# op-amp.net
KiCad netlist of a schematic drawn in Altium Designer
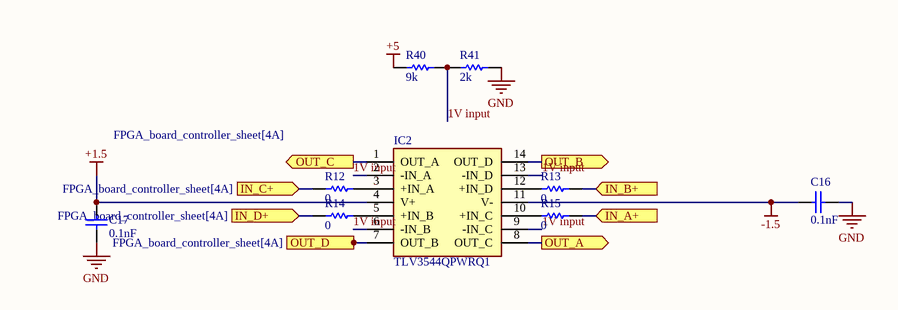
[diagram p0: op-amp.SchDoc]

(export (version "E")
  (design (tool "Eeschema 10.0.6"))
  (components
    (comp (ref "C16")
      (value "0.1nF")
      (footprint "C0603")
      (libsource (lib "Schlib_FPGA_Controller") (part "Cap"))
    )
    (comp (ref "C17")
      (value "0.1nF")
      (footprint "C0603")
      (libsource (lib "Schlib_FPGA_Controller") (part "Cap"))
    )
    (comp (ref "IC2")
      (value "TLV3544QPWRQ1")
      (footprint "SamacSys:SOP65P640X120-14N")
      (description "Integrated Circuit")
      (fields (field (name "MOUSER PART NUMBER") "595-TLV3544QPWRQ1"))
      (libsource (lib "Schlib_FPGA_Controller") (part "TLV3544QPWRQ1"))
    )
    (comp (ref "R12")
      (value "0")
      (footprint "R0603")
      (libsource (lib "Schlib_FPGA_Controller") (part "Resistor"))
    )
    (comp (ref "R13")
      (value "0")
      (footprint "R0603")
      (libsource (lib "Schlib_FPGA_Controller") (part "Resistor"))
    )
    (comp (ref "R14")
      (value "0")
      (footprint "R0603")
      (libsource (lib "Schlib_FPGA_Controller") (part "Resistor"))
    )
    (comp (ref "R15")
      (value "0")
      (footprint "R0603")
      (libsource (lib "Schlib_FPGA_Controller") (part "Resistor"))
    )
    (comp (ref "R40")
      (value "9k")
      (footprint "R0603")
      (libsource (lib "Schlib_FPGA_Controller") (part "Resistor"))
    )
    (comp (ref "R41")
      (value "2k")
      (footprint "R0603")
      (libsource (lib "Schlib_FPGA_Controller") (part "Resistor"))
    )
  )
  (nets
    (net (code "1") (name "+1.5") (class "Default")
      (node (ref "C17") (pin "2") (pinfunction "2_2") (pintype "passive"))
      (node (ref "IC2") (pin "4") (pinfunction "V+_4") (pintype "passive"))
    )
    (net (code "2") (name "+5") (class "Default")
      (node (ref "R40") (pin "1") (pinfunction "1_1") (pintype "passive"))
    )
    (net (code "3") (name "-1.5") (class "Default")
      (node (ref "C16") (pin "1") (pinfunction "1_1") (pintype "passive"))
      (node (ref "IC2") (pin "11") (pinfunction "V-_11") (pintype "passive"))
    )
    (net (code "4") (name "/1V input") (class "Default")
      (node (ref "IC2") (pin "13") (pinfunction "-IN_D_13") (pintype "passive"))
      (node (ref "IC2") (pin "2") (pinfunction "-IN_A_2") (pintype "passive"))
      (node (ref "IC2") (pin "6") (pinfunction "-IN_B_6") (pintype "passive"))
      (node (ref "IC2") (pin "9") (pinfunction "-IN_C_9") (pintype "passive"))
      (node (ref "R40") (pin "2") (pinfunction "2_2") (pintype "passive"))
      (node (ref "R41") (pin "1") (pinfunction "1_1") (pintype "passive"))
    )
    (net (code "5") (name "/IN_A+") (class "Default")
      (node (ref "R15") (pin "2") (pinfunction "2_2") (pintype "passive"))
    )
    (net (code "6") (name "/IN_B+") (class "Default")
      (node (ref "R13") (pin "2") (pinfunction "2_2") (pintype "passive"))
    )
    (net (code "7") (name "/IN_C+") (class "Default")
      (node (ref "R12") (pin "1") (pinfunction "1_1") (pintype "passive"))
    )
    (net (code "8") (name "/IN_D+") (class "Default")
      (node (ref "R14") (pin "1") (pinfunction "1_1") (pintype "passive"))
    )
    (net (code "9") (name "/OUT_A") (class "Default")
      (node (ref "IC2") (pin "8") (pinfunction "OUT_C_8") (pintype "passive"))
    )
    (net (code "10") (name "/OUT_B") (class "Default")
      (node (ref "IC2") (pin "14") (pinfunction "OUT_D_14") (pintype "passive"))
    )
    (net (code "11") (name "/OUT_C") (class "Default")
      (node (ref "IC2") (pin "1") (pinfunction "OUT_A_1") (pintype "passive"))
    )
    (net (code "12") (name "/OUT_D") (class "Default")
      (node (ref "IC2") (pin "7") (pinfunction "OUT_B_7") (pintype "passive"))
    )
    (net (code "13") (name "GND") (class "Default")
      (node (ref "C16") (pin "2") (pinfunction "2_2") (pintype "passive"))
      (node (ref "C17") (pin "1") (pinfunction "1_1") (pintype "passive"))
      (node (ref "R41") (pin "2") (pinfunction "2_2") (pintype "passive"))
    )
    (net (code "14") (name "Net-(IC2-+IN_A)") (class "Default")
      (node (ref "IC2") (pin "3") (pinfunction "+IN_A_3") (pintype "passive"))
      (node (ref "R12") (pin "2") (pinfunction "2_2") (pintype "passive"))
    )
    (net (code "15") (name "Net-(IC2-+IN_B)") (class "Default")
      (node (ref "IC2") (pin "5") (pinfunction "+IN_B_5") (pintype "passive"))
      (node (ref "R14") (pin "2") (pinfunction "2_2") (pintype "passive"))
    )
    (net (code "16") (name "Net-(IC2-+IN_C)") (class "Default")
      (node (ref "IC2") (pin "10") (pinfunction "+IN_C_10") (pintype "passive"))
      (node (ref "R15") (pin "1") (pinfunction "1_1") (pintype "passive"))
    )
    (net (code "17") (name "Net-(IC2-+IN_D)") (class "Default")
      (node (ref "IC2") (pin "12") (pinfunction "+IN_D_12") (pintype "passive"))
      (node (ref "R13") (pin "1") (pinfunction "1_1") (pintype "passive"))
    )
  )
)
